# MLX90363.net
KiCad netlist of a schematic drawn in Altium Designer
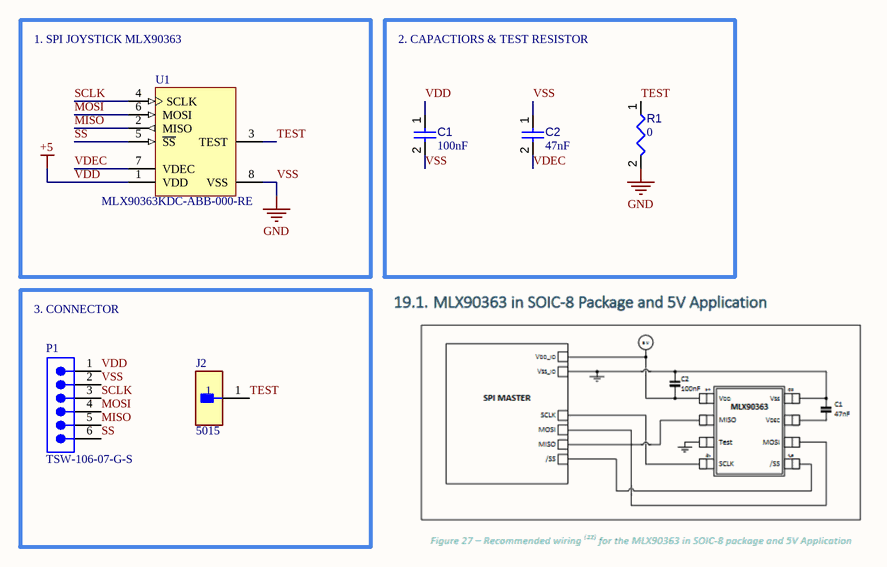
[diagram p0: MLX90363.SchDoc]

(export (version "E")
  (design (tool "Eeschema 10.0.6"))
  (components
    (comp (ref "C1")
      (value "100nF")
      (footprint "CAPC0402(1005)60_L")
      (description "Chip Capacitor, 100nF +/-20%, 25V, 0402, Thickness 0.6 mm")
      (fields (field (name "TOLERANCE") "10%") (field (name "Comment") "Capacitor 100nF +/-20% 25V 0402"))
      (libsource (lib "SUBC") (part "CAP-NP-2"))
    )
    (comp (ref "C2")
      (value "47nF")
      (footprint "CAPC0402(1005)60_L")
      (description "Chip Capacitor, 47nF +/-20%, 50V, 0402, Thickness 0.6 mm")
      (fields (field (name "TOLERANCE") "20%") (field (name "Comment") "Capacitor 47nF +/-20% 50V 0402"))
      (libsource (lib "SUBC") (part "CAP-NP-2"))
    )
    (comp (ref "J2")
      (value "5015")
      (footprint "FP-5015-MFG")
      (description "Test Point Micro Mini SMT Phos Bronze/Silver 1000pc Tape & Reel")
      (libsource (lib "SUBC") (part "dd45045ce8184df9e99e12baf3f412c"))
    )
    (comp (ref "P1")
      (value "TSW-106-07-G-S")
      (footprint "SMTC-TSW-106-07-X-S")
      (description "Conn Unshrouded Header HDR 6 POS 2.54mm Solder ST Top Entry Thru-Hole Bag")
      (libsource (lib "SUBC") (part "SMTC-TSW-106-X-X-S-X"))
    )
    (comp (ref "R1")
      (value "0")
      (footprint "RESC0402(1005)_L")
      (description "Jumper 0402 (1005 Metric)")
      (fields (field (name "Comment") "0R2J"))
      (libsource (lib "SUBC") (part "0R2J"))
    )
    (comp (ref "U1")
      (value "MLX90363KDC-ABB-000-RE")
      (footprint "MEX-DC-8_L")
      (description "Hall Effect Sensor, 20mT Min, 70mT Max, 0.4-2.9V, CMOS, Rectangular, 8 Pin, Surface Mount")
      (libsource (lib "SUBC") (part "MEX-MLX90363-8"))
    )
  )
  (nets
    (net (code "1") (name "+5") (class "Default")
      (node (ref "C1") (pin "1") (pinfunction "1_1") (pintype "passive"))
      (node (ref "P1") (pin "1") (pinfunction "1_1") (pintype "passive"))
      (node (ref "U1") (pin "1") (pinfunction "VDD_1") (pintype "power_in"))
    )
    (net (code "2") (name "/MISO") (class "Default")
      (node (ref "P1") (pin "5") (pinfunction "5_5") (pintype "passive"))
      (node (ref "U1") (pin "2") (pinfunction "MISO_2") (pintype "output"))
    )
    (net (code "3") (name "/MOSI") (class "Default")
      (node (ref "P1") (pin "4") (pinfunction "4_4") (pintype "passive"))
      (node (ref "U1") (pin "6") (pinfunction "MOSI_6") (pintype "input"))
    )
    (net (code "4") (name "/SCLK") (class "Default")
      (node (ref "P1") (pin "3") (pinfunction "3_3") (pintype "passive"))
      (node (ref "U1") (pin "4") (pinfunction "SCLK_4") (pintype "input"))
    )
    (net (code "5") (name "/SS") (class "Default")
      (node (ref "P1") (pin "6") (pinfunction "6_6") (pintype "passive"))
      (node (ref "U1") (pin "5") (pinfunction "~{SS}_5") (pintype "input"))
    )
    (net (code "6") (name "/TEST") (class "Default")
      (node (ref "J2") (pin "1") (pinfunction "1_1") (pintype "passive"))
      (node (ref "R1") (pin "1") (pinfunction "1_1") (pintype "passive"))
      (node (ref "U1") (pin "3") (pinfunction "TEST_3") (pintype "passive"))
    )
    (net (code "7") (name "/VDEC") (class "Default")
      (node (ref "C2") (pin "2") (pinfunction "2_2") (pintype "passive"))
      (node (ref "U1") (pin "7") (pinfunction "VDEC_7") (pintype "power_in"))
    )
    (net (code "8") (name "GND") (class "Default")
      (node (ref "C1") (pin "2") (pinfunction "2_2") (pintype "passive"))
      (node (ref "C2") (pin "1") (pinfunction "1_1") (pintype "passive"))
      (node (ref "P1") (pin "2") (pinfunction "2_2") (pintype "passive"))
      (node (ref "R1") (pin "2") (pinfunction "2_2") (pintype "passive"))
      (node (ref "U1") (pin "8") (pinfunction "VSS_8") (pintype "power_in"))
    )
  )
)
